# Digital_Circuitry.net
KiCad netlist of a schematic drawn in Altium Designer
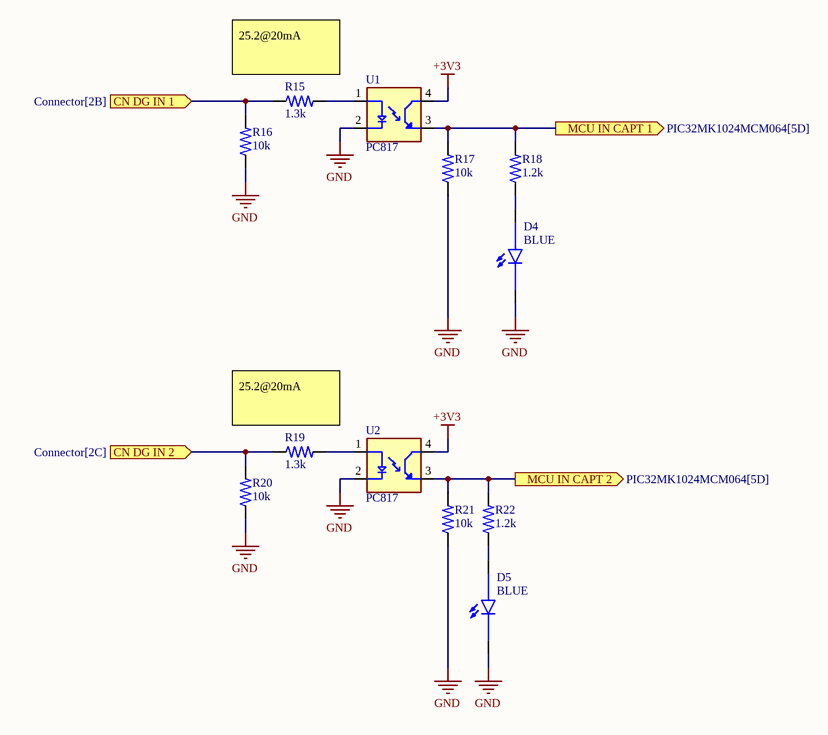
[diagram p0: Digital Circuitry.SchDoc]

(export (version "E")
  (design (tool "Eeschema 10.0.6"))
  (components
    (comp (ref "D4")
      (value "BLUE")
      (footprint "LED 0805")
      (description "LED Uni-Color Green 4-Pin Chip 0805 T/R")
      (fields (field (name "MP") "597-3305-607F"))
      (libsource (lib "LEDs SMD") (part "LED 0805"))
    )
    (comp (ref "D5")
      (value "BLUE")
      (footprint "LED 0805")
      (description "LED Uni-Color Green 4-Pin Chip 0805 T/R")
      (fields (field (name "MP") "597-3305-607F"))
      (libsource (lib "LEDs SMD") (part "LED 0805"))
    )
    (comp (ref "R15")
      (value "1.3k")
      (footprint "0805")
      (fields
        (field (name "MP") "2-2176053-0")
        (field (name "TOLERANCE") "1%")
        (field (name "MF") "TE Connectivity")
      )
      (libsource (lib "Resistors SMD") (part "0805_Resistor"))
    )
    (comp (ref "R16")
      (value "10k")
      (footprint "0805")
      (fields
        (field (name "MP") "2-2176053-0")
        (field (name "TOLERANCE") "1%")
        (field (name "MF") "TE Connectivity")
      )
      (libsource (lib "Resistors SMD") (part "0805_Resistor"))
    )
    (comp (ref "R17")
      (value "10k")
      (footprint "0805")
      (fields
        (field (name "MP") "2-2176053-0")
        (field (name "TOLERANCE") "1%")
        (field (name "MF") "TE Connectivity")
      )
      (libsource (lib "Resistors SMD") (part "0805_Resistor"))
    )
    (comp (ref "R18")
      (value "1.2k")
      (footprint "0805")
      (fields
        (field (name "MP") "2-2176053-0")
        (field (name "TOLERANCE") "1%")
        (field (name "MF") "TE Connectivity")
      )
      (libsource (lib "Resistors SMD") (part "0805_Resistor"))
    )
    (comp (ref "R19")
      (value "1.3k")
      (footprint "0805")
      (fields
        (field (name "MP") "2-2176053-0")
        (field (name "TOLERANCE") "1%")
        (field (name "MF") "TE Connectivity")
      )
      (libsource (lib "Resistors SMD") (part "0805_Resistor"))
    )
    (comp (ref "R20")
      (value "10k")
      (footprint "0805")
      (fields
        (field (name "MP") "2-2176053-0")
        (field (name "TOLERANCE") "1%")
        (field (name "MF") "TE Connectivity")
      )
      (libsource (lib "Resistors SMD") (part "0805_Resistor"))
    )
    (comp (ref "R21")
      (value "10k")
      (footprint "0805")
      (fields
        (field (name "MP") "2-2176053-0")
        (field (name "TOLERANCE") "1%")
        (field (name "MF") "TE Connectivity")
      )
      (libsource (lib "Resistors SMD") (part "0805_Resistor"))
    )
    (comp (ref "R22")
      (value "1.2k")
      (footprint "0805")
      (fields
        (field (name "MP") "2-2176053-0")
        (field (name "TOLERANCE") "1%")
        (field (name "MF") "TE Connectivity")
      )
      (libsource (lib "Resistors SMD") (part "0805_Resistor"))
    )
    (comp (ref "U1")
      (value "PC817")
      (footprint "PC817")
      (description "Optoisolator Transistor Output 5000Vrms 1 Channel 4-SMD")
      (fields (field (name "MP") "PC817XI") (field (name "MF") "Sharp Microelectronics"))
      (libsource (lib "Optocoupler SMD") (part "PC817"))
    )
    (comp (ref "U2")
      (value "PC817")
      (footprint "PC817")
      (description "Optoisolator Transistor Output 5000Vrms 1 Channel 4-SMD")
      (fields (field (name "MP") "PC817XI") (field (name "MF") "Sharp Microelectronics"))
      (libsource (lib "Optocoupler SMD") (part "PC817"))
    )
  )
  (nets
    (net (code "1") (name "+3V3") (class "Default")
      (node (ref "U1") (pin "4") (pinfunction "CT_4") (pintype "passive"))
      (node (ref "U2") (pin "4") (pinfunction "CT_4") (pintype "passive"))
    )
    (net (code "2") (name "/CN DG IN 1") (class "Default")
      (node (ref "R15") (pin "1") (pinfunction "1_1") (pintype "passive"))
      (node (ref "R16") (pin "2") (pinfunction "2_2") (pintype "passive"))
    )
    (net (code "3") (name "/CN DG IN 2") (class "Default")
      (node (ref "R19") (pin "1") (pinfunction "1_1") (pintype "passive"))
      (node (ref "R20") (pin "2") (pinfunction "2_2") (pintype "passive"))
    )
    (net (code "4") (name "/MCU IN CAPT 1") (class "Default")
      (node (ref "R17") (pin "2") (pinfunction "2_2") (pintype "passive"))
      (node (ref "R18") (pin "2") (pinfunction "2_2") (pintype "passive"))
      (node (ref "U1") (pin "3") (pinfunction "ET_3") (pintype "passive"))
    )
    (net (code "5") (name "/MCU IN CAPT 2") (class "Default")
      (node (ref "R21") (pin "2") (pinfunction "2_2") (pintype "passive"))
      (node (ref "R22") (pin "2") (pinfunction "2_2") (pintype "passive"))
      (node (ref "U2") (pin "3") (pinfunction "ET_3") (pintype "passive"))
    )
    (net (code "6") (name "GND") (class "Default")
      (node (ref "D4") (pin "C") (pinfunction "C_C") (pintype "passive"))
      (node (ref "D5") (pin "C") (pinfunction "C_C") (pintype "passive"))
      (node (ref "R16") (pin "1") (pinfunction "1_1") (pintype "passive"))
      (node (ref "R17") (pin "1") (pinfunction "1_1") (pintype "passive"))
      (node (ref "R20") (pin "1") (pinfunction "1_1") (pintype "passive"))
      (node (ref "R21") (pin "1") (pinfunction "1_1") (pintype "passive"))
      (node (ref "U1") (pin "2") (pinfunction "C_2") (pintype "passive"))
      (node (ref "U2") (pin "2") (pinfunction "C_2") (pintype "passive"))
    )
    (net (code "7") (name "Net-(D4-PadA)") (class "Default")
      (node (ref "D4") (pin "A") (pinfunction "A_A") (pintype "passive"))
      (node (ref "R18") (pin "1") (pinfunction "1_1") (pintype "passive"))
    )
    (net (code "8") (name "Net-(D5-PadA)") (class "Default")
      (node (ref "D5") (pin "A") (pinfunction "A_A") (pintype "passive"))
      (node (ref "R22") (pin "1") (pinfunction "1_1") (pintype "passive"))
    )
    (net (code "9") (name "Net-(U1-A)") (class "Default")
      (node (ref "R15") (pin "2") (pinfunction "2_2") (pintype "passive"))
      (node (ref "U1") (pin "1") (pinfunction "A_1") (pintype "passive"))
    )
    (net (code "10") (name "Net-(U2-A)") (class "Default")
      (node (ref "R19") (pin "2") (pinfunction "2_2") (pintype "passive"))
      (node (ref "U2") (pin "1") (pinfunction "A_1") (pintype "passive"))
    )
  )
)
